# 04-Switch_RJ45.net
KiCad netlist of a schematic drawn in Altium Designer
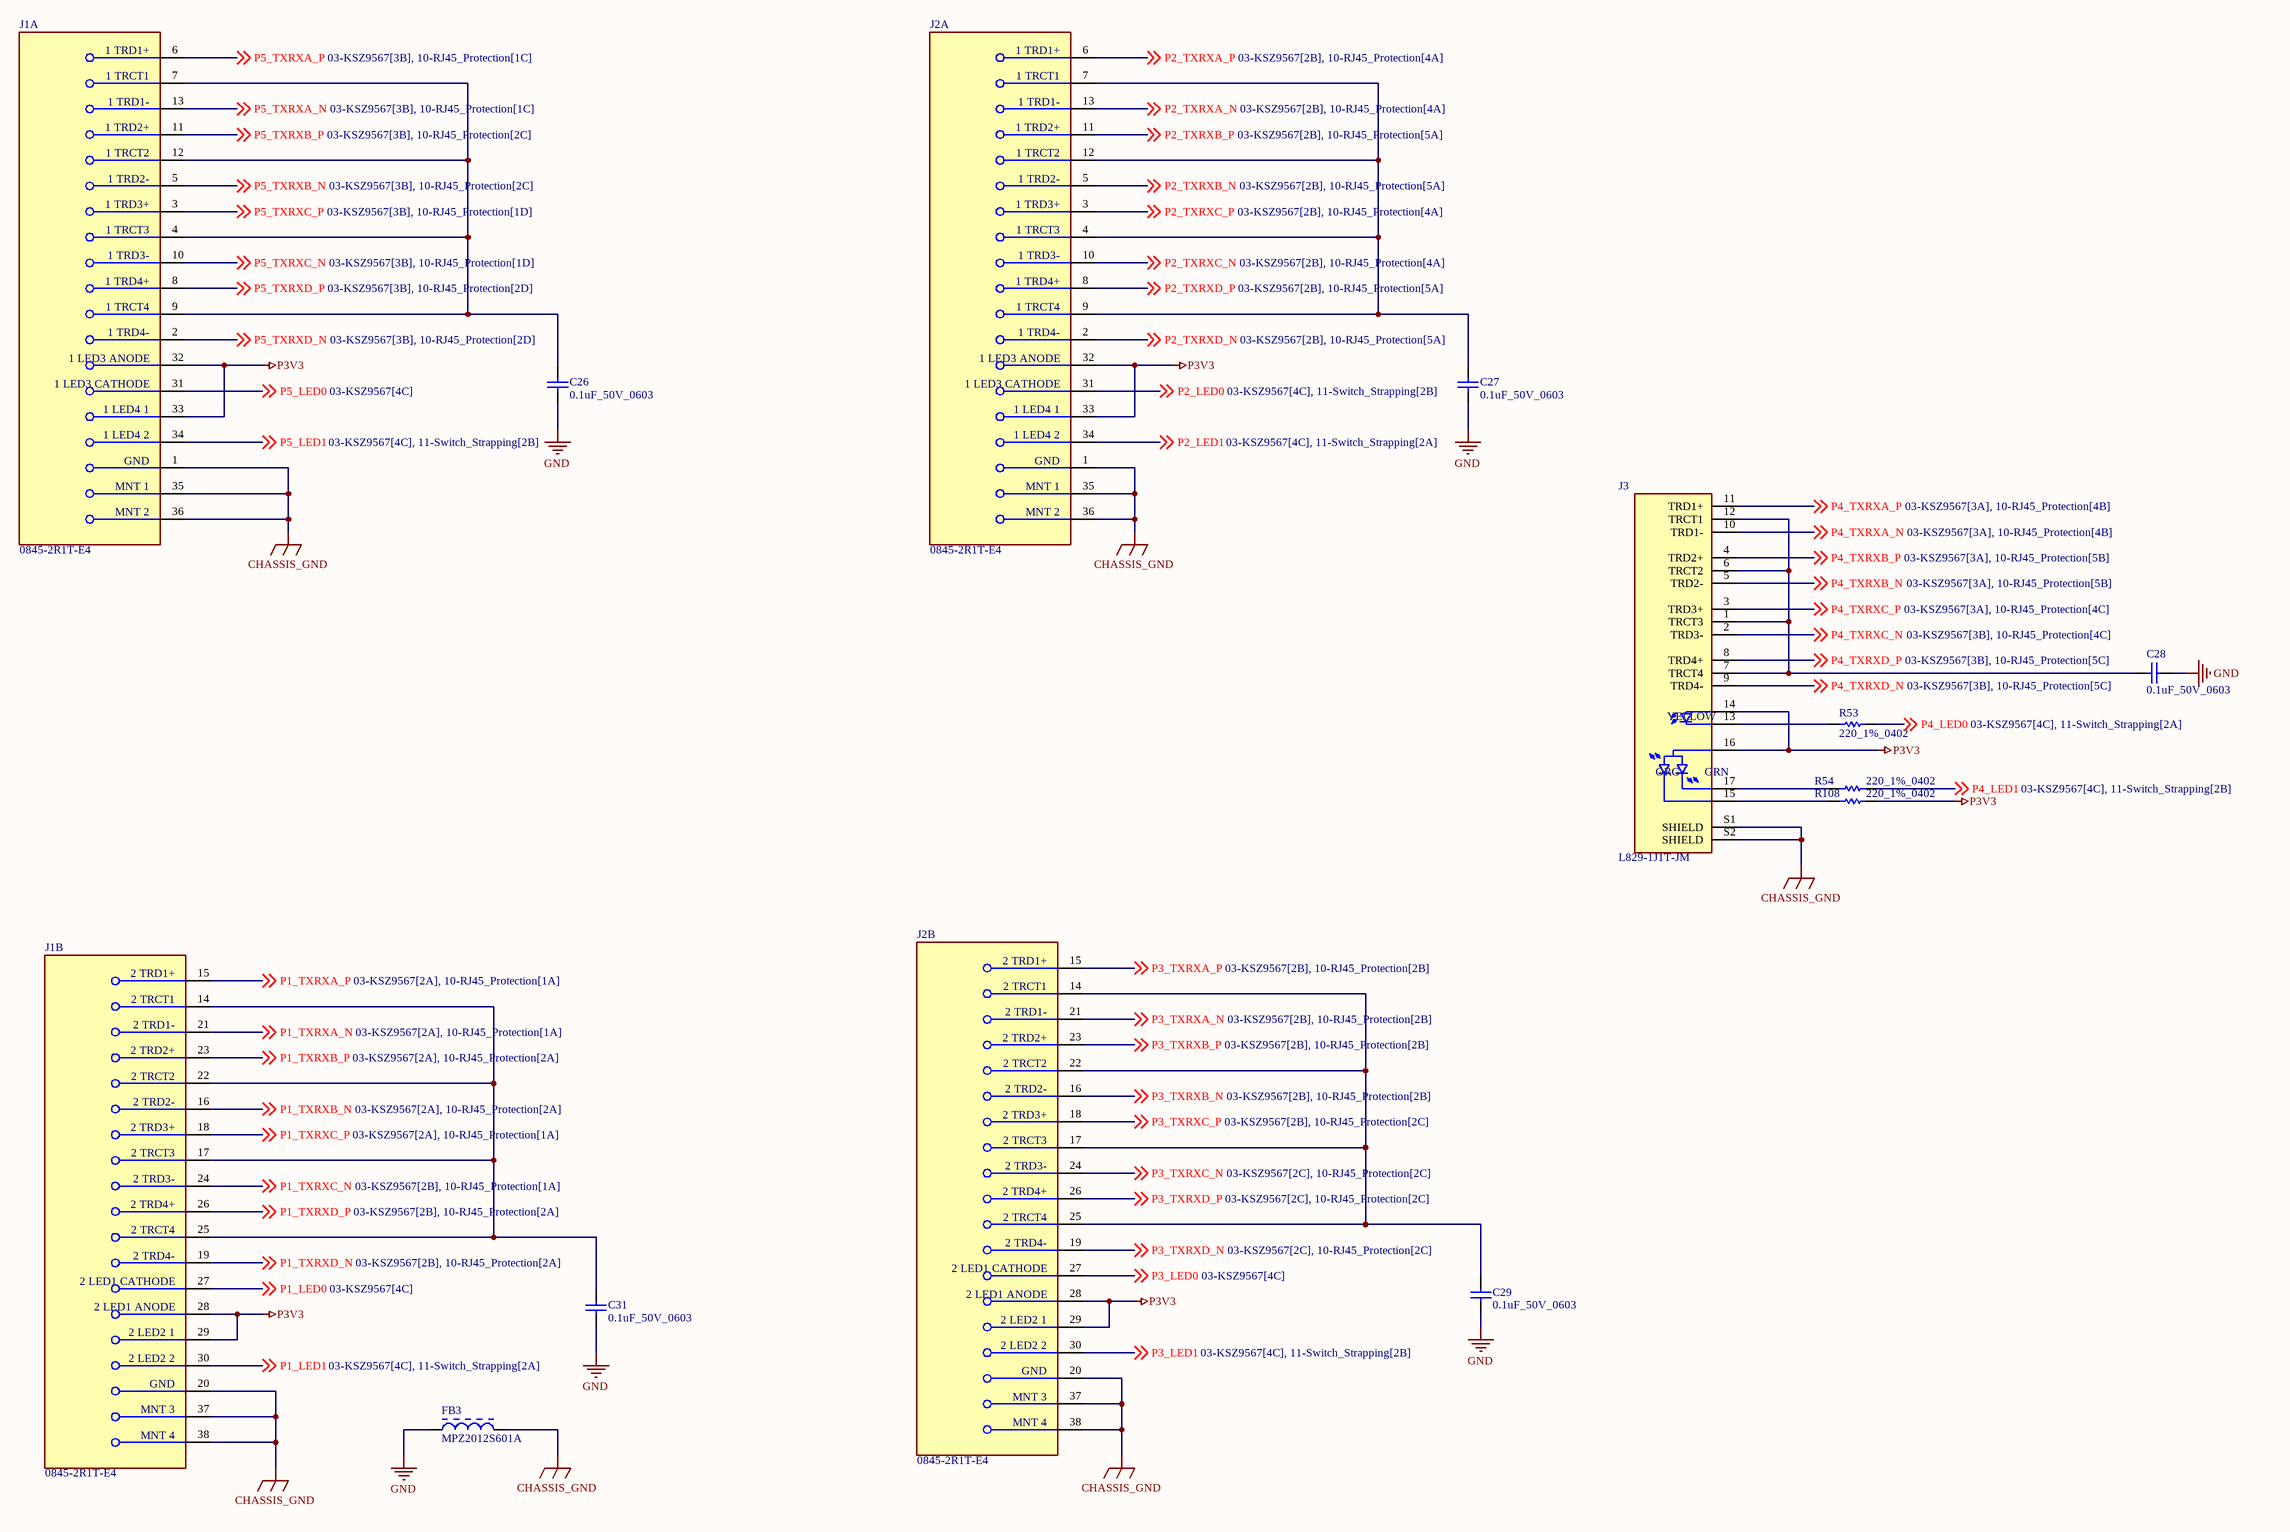
[diagram p0: 04-Switch_RJ45.SchDoc]

(export (version "E")
  (design (tool "Eeschema 10.0.6"))
  (components
    (comp (ref "C26")
      (value "0.1uF_50V_0603")
      (footprint "CAPC1608X90X35ML10T15")
      (description "Chip Capacitor, 0.1 uF, +/- 10%, 50 V, -55 to 125 degC, 0603 (1608 Metric), RoHS, Tape and Reel")
      (fields (field (name "TOLERANCE") "10%") (field (name "VOLTAGE") "50V"))
      (libsource (lib "Altium Content Vault") (part "CAP-NP-2"))
    )
    (comp (ref "C27")
      (value "0.1uF_50V_0603")
      (footprint "CAPC1608X90X35ML10T15")
      (description "Chip Capacitor, 0.1 uF, +/- 10%, 50 V, -55 to 125 degC, 0603 (1608 Metric), RoHS, Tape and Reel")
      (fields (field (name "TOLERANCE") "10%") (field (name "VOLTAGE") "50V"))
      (libsource (lib "Altium Content Vault") (part "CAP-NP-2"))
    )
    (comp (ref "C28")
      (value "0.1uF_50V_0603")
      (footprint "CAPC1608X90X35ML10T15")
      (description "Chip Capacitor, 0.1 uF, +/- 10%, 50 V, -55 to 125 degC, 0603 (1608 Metric), RoHS, Tape and Reel")
      (fields (field (name "TOLERANCE") "10%") (field (name "VOLTAGE") "50V"))
      (libsource (lib "Altium Content Vault") (part "CAP-NP-2"))
    )
    (comp (ref "C29")
      (value "0.1uF_50V_0603")
      (footprint "CAPC1608X90X35ML10T15")
      (description "Chip Capacitor, 0.1 uF, +/- 10%, 50 V, -55 to 125 degC, 0603 (1608 Metric), RoHS, Tape and Reel")
      (fields (field (name "TOLERANCE") "10%") (field (name "VOLTAGE") "50V"))
      (libsource (lib "Altium Content Vault") (part "CAP-NP-2"))
    )
    (comp (ref "C31")
      (value "0.1uF_50V_0603")
      (footprint "CAPC1608X90X35ML10T15")
      (description "Chip Capacitor, 0.1 uF, +/- 10%, 50 V, -55 to 125 degC, 0603 (1608 Metric), RoHS, Tape and Reel")
      (fields (field (name "TOLERANCE") "10%") (field (name "VOLTAGE") "50V"))
      (libsource (lib "Altium Content Vault") (part "CAP-NP-2"))
    )
    (comp (ref "FB3")
      (value "MPZ2012S601A")
      (footprint "TDK-MPZ2012_V")
      (fields (field (name "TOLERANCE") "25%") (field (name "MANUFACTURER") "TDK"))
      (libsource (lib "Altium Content Vault") (part "BEAD-2"))
    )
    (comp (ref "J1")
      (value "0845-2R1T-E4")
      (footprint "FP-0845-2R1T-E4-MFG")
      (description "CONN MAGJACK 2PORT 1000 BASE-T")
      (fields
        (field (name "MANUFACTURER") "Bel Fuse")
        (field (name "OCTOPART") "https://octopart.com/0845-2r1t-e4-bel+fuse-10528446")
      )
      (libsource (lib "Altium Content Vault") (part "f9656fd82f206e5257674b7adff4f5e"))
    )
    (comp (ref "J2")
      (value "0845-2R1T-E4")
      (footprint "FP-0845-2R1T-E4-MFG")
      (description "CONN MAGJACK 2PORT 1000 BASE-T")
      (fields
        (field (name "MANUFACTURER") "Bel Fuse")
        (field (name "OCTOPART") "https://octopart.com/0845-2r1t-e4-bel+fuse-10528446")
      )
      (libsource (lib "Altium Content Vault") (part "f9656fd82f206e5257674b7adff4f5e"))
    )
    (comp (ref "J3")
      (value "L829-1J1T-JM")
      (footprint "BEL_L829-1J1T-JM")
      (description "MagJack 2.5GBASE-T ¦ 1X1 ¦ OG/Y LED ¦ -40 to 85C ¦ RoHS")
      (fields
        (field (name "DIGI-KEY_PART_NUMBER") "507-2068-ND")
        (field (name "MF") "Bel Magnetic Solutions")
      )
      (libsource (lib "SnapEDAsch") (part "L829-1J1T-JM"))
    )
    (comp (ref "R53")
      (value "220_1%_0402")
      (footprint "RESC1005X40X25LL10T10")
      (fields (field (name "PART NUMBER") "RK73H1ETTP2200F") (field (name "MANUFACTURER") "KOA Speer"))
      (libsource (lib "Altium Content Vault") (part "RES"))
    )
    (comp (ref "R54")
      (value "220_1%_0402")
      (footprint "RESC1005X40X25LL10T10")
      (fields (field (name "PART NUMBER") "RK73H1ETTP2200F") (field (name "MANUFACTURER") "KOA Speer"))
      (libsource (lib "Altium Content Vault") (part "RES"))
    )
    (comp (ref "R108")
      (value "220_1%_0402")
      (footprint "RESC1005X40X25LL10T10")
      (fields (field (name "PART NUMBER") "RK73H1ETTP2200F") (field (name "MANUFACTURER") "KOA Speer"))
      (libsource (lib "Altium Content Vault") (part "RES"))
    )
  )
  (nets
    (net (code "1") (name "CHASSIS_GND") (class "Default")
      (node (ref "FB3") (pin "2") (pinfunction "2_2") (pintype "passive"))
      (node (ref "J1") (pin "1") (pinfunction "GND_1") (pintype "power_in"))
      (node (ref "J1") (pin "20") (pinfunction "GND_20") (pintype "power_in"))
      (node (ref "J1") (pin "35") (pinfunction "MNT_1_35") (pintype "passive"))
      (node (ref "J1") (pin "36") (pinfunction "MNT_2_36") (pintype "passive"))
      (node (ref "J1") (pin "37") (pinfunction "MNT_3_37") (pintype "passive"))
      (node (ref "J1") (pin "38") (pinfunction "MNT_4_38") (pintype "passive"))
      (node (ref "J2") (pin "1") (pinfunction "GND_1") (pintype "power_in"))
      (node (ref "J2") (pin "20") (pinfunction "GND_20") (pintype "power_in"))
      (node (ref "J2") (pin "35") (pinfunction "MNT_1_35") (pintype "passive"))
      (node (ref "J2") (pin "36") (pinfunction "MNT_2_36") (pintype "passive"))
      (node (ref "J2") (pin "37") (pinfunction "MNT_3_37") (pintype "passive"))
      (node (ref "J2") (pin "38") (pinfunction "MNT_4_38") (pintype "passive"))
      (node (ref "J3") (pin "S1") (pinfunction "SHIELD_S1") (pintype "passive"))
      (node (ref "J3") (pin "S2") (pinfunction "SHIELD_S2") (pintype "passive"))
    )
    (net (code "2") (name "GND") (class "Default")
      (node (ref "C26") (pin "1") (pinfunction "1_1") (pintype "passive"))
      (node (ref "C27") (pin "1") (pinfunction "1_1") (pintype "passive"))
      (node (ref "C28") (pin "1") (pinfunction "1_1") (pintype "passive"))
      (node (ref "C29") (pin "1") (pinfunction "1_1") (pintype "passive"))
      (node (ref "C31") (pin "1") (pinfunction "1_1") (pintype "passive"))
      (node (ref "FB3") (pin "1") (pinfunction "1_1") (pintype "passive"))
    )
    (net (code "3") (name "Net-(J1A-1_TRCT1)") (class "Default")
      (node (ref "C26") (pin "2") (pinfunction "2_2") (pintype "passive"))
      (node (ref "J1") (pin "12") (pinfunction "1_TRCT2_12") (pintype "passive"))
      (node (ref "J1") (pin "4") (pinfunction "1_TRCT3_4") (pintype "passive"))
      (node (ref "J1") (pin "7") (pinfunction "1_TRCT1_7") (pintype "passive"))
      (node (ref "J1") (pin "9") (pinfunction "1_TRCT4_9") (pintype "passive"))
    )
    (net (code "4") (name "Net-(J1B-2_TRCT1)") (class "Default")
      (node (ref "C31") (pin "2") (pinfunction "2_2") (pintype "passive"))
      (node (ref "J1") (pin "14") (pinfunction "2_TRCT1_14") (pintype "passive"))
      (node (ref "J1") (pin "17") (pinfunction "2_TRCT3_17") (pintype "passive"))
      (node (ref "J1") (pin "22") (pinfunction "2_TRCT2_22") (pintype "passive"))
      (node (ref "J1") (pin "25") (pinfunction "2_TRCT4_25") (pintype "passive"))
    )
    (net (code "5") (name "Net-(J2A-1_TRCT1)") (class "Default")
      (node (ref "C27") (pin "2") (pinfunction "2_2") (pintype "passive"))
      (node (ref "J2") (pin "12") (pinfunction "1_TRCT2_12") (pintype "passive"))
      (node (ref "J2") (pin "4") (pinfunction "1_TRCT3_4") (pintype "passive"))
      (node (ref "J2") (pin "7") (pinfunction "1_TRCT1_7") (pintype "passive"))
      (node (ref "J2") (pin "9") (pinfunction "1_TRCT4_9") (pintype "passive"))
    )
    (net (code "6") (name "Net-(J2B-2_TRCT1)") (class "Default")
      (node (ref "C29") (pin "2") (pinfunction "2_2") (pintype "passive"))
      (node (ref "J2") (pin "14") (pinfunction "2_TRCT1_14") (pintype "passive"))
      (node (ref "J2") (pin "17") (pinfunction "2_TRCT3_17") (pintype "passive"))
      (node (ref "J2") (pin "22") (pinfunction "2_TRCT2_22") (pintype "passive"))
      (node (ref "J2") (pin "25") (pinfunction "2_TRCT4_25") (pintype "passive"))
    )
    (net (code "7") (name "Net-(J3-GK_1)") (class "Default")
      (node (ref "J3") (pin "17") (pinfunction "GK_1_17") (pintype "passive"))
      (node (ref "R54") (pin "1") (pinfunction "1_1") (pintype "passive"))
    )
    (net (code "8") (name "Net-(J3-OK_1)") (class "Default")
      (node (ref "J3") (pin "15") (pinfunction "OK_1_15") (pintype "passive"))
      (node (ref "R108") (pin "1") (pinfunction "1_1") (pintype "passive"))
    )
    (net (code "9") (name "Net-(J3-TRCT1)") (class "Default")
      (node (ref "C28") (pin "2") (pinfunction "2_2") (pintype "passive"))
      (node (ref "J3") (pin "1") (pinfunction "TRCT3_1") (pintype "passive"))
      (node (ref "J3") (pin "12") (pinfunction "TRCT1_12") (pintype "passive"))
      (node (ref "J3") (pin "6") (pinfunction "TRCT2_6") (pintype "passive"))
      (node (ref "J3") (pin "7") (pinfunction "TRCT4_7") (pintype "passive"))
    )
    (net (code "10") (name "Net-(J3-YK_1)") (class "Default")
      (node (ref "J3") (pin "13") (pinfunction "YK_1_13") (pintype "passive"))
      (node (ref "R53") (pin "1") (pinfunction "1_1") (pintype "passive"))
    )
    (net (code "11") (name "P1_LED0") (class "Default")
      (node (ref "J1") (pin "27") (pinfunction "2_LED1_CATHODE_27") (pintype "passive"))
    )
    (net (code "12") (name "P1_LED1") (class "Default")
      (node (ref "J1") (pin "30") (pinfunction "2_LED2_2_30") (pintype "passive"))
    )
    (net (code "13") (name "P1_TXRXA_N") (class "Default")
      (node (ref "J1") (pin "21") (pinfunction "2_TRD1-_21") (pintype "passive"))
    )
    (net (code "14") (name "P1_TXRXA_P") (class "Default")
      (node (ref "J1") (pin "15") (pinfunction "2_TRD1+_15") (pintype "passive"))
    )
    (net (code "15") (name "P1_TXRXB_N") (class "Default")
      (node (ref "J1") (pin "16") (pinfunction "2_TRD2-_16") (pintype "passive"))
    )
    (net (code "16") (name "P1_TXRXB_P") (class "Default")
      (node (ref "J1") (pin "23") (pinfunction "2_TRD2+_23") (pintype "passive"))
    )
    (net (code "17") (name "P1_TXRXC_N") (class "Default")
      (node (ref "J1") (pin "24") (pinfunction "2_TRD3-_24") (pintype "passive"))
    )
    (net (code "18") (name "P1_TXRXC_P") (class "Default")
      (node (ref "J1") (pin "18") (pinfunction "2_TRD3+_18") (pintype "passive"))
    )
    (net (code "19") (name "P1_TXRXD_N") (class "Default")
      (node (ref "J1") (pin "19") (pinfunction "2_TRD4-_19") (pintype "passive"))
    )
    (net (code "20") (name "P1_TXRXD_P") (class "Default")
      (node (ref "J1") (pin "26") (pinfunction "2_TRD4+_26") (pintype "passive"))
    )
    (net (code "21") (name "P2_LED0") (class "Default")
      (node (ref "J2") (pin "31") (pinfunction "1_LED3_CATHODE_31") (pintype "passive"))
    )
    (net (code "22") (name "P2_LED1") (class "Default")
      (node (ref "J2") (pin "34") (pinfunction "1_LED4_2_34") (pintype "passive"))
    )
    (net (code "23") (name "P2_TXRXA_N") (class "Default")
      (node (ref "J2") (pin "13") (pinfunction "1_TRD1-_13") (pintype "passive"))
    )
    (net (code "24") (name "P2_TXRXA_P") (class "Default")
      (node (ref "J2") (pin "6") (pinfunction "1_TRD1+_6") (pintype "passive"))
    )
    (net (code "25") (name "P2_TXRXB_N") (class "Default")
      (node (ref "J2") (pin "5") (pinfunction "1_TRD2-_5") (pintype "passive"))
    )
    (net (code "26") (name "P2_TXRXB_P") (class "Default")
      (node (ref "J2") (pin "11") (pinfunction "1_TRD2+_11") (pintype "passive"))
    )
    (net (code "27") (name "P2_TXRXC_N") (class "Default")
      (node (ref "J2") (pin "10") (pinfunction "1_TRD3-_10") (pintype "passive"))
    )
    (net (code "28") (name "P2_TXRXC_P") (class "Default")
      (node (ref "J2") (pin "3") (pinfunction "1_TRD3+_3") (pintype "passive"))
    )
    (net (code "29") (name "P2_TXRXD_N") (class "Default")
      (node (ref "J2") (pin "2") (pinfunction "1_TRD4-_2") (pintype "passive"))
    )
    (net (code "30") (name "P2_TXRXD_P") (class "Default")
      (node (ref "J2") (pin "8") (pinfunction "1_TRD4+_8") (pintype "passive"))
    )
    (net (code "31") (name "P3V3") (class "Default")
      (node (ref "J1") (pin "28") (pinfunction "2_LED1_ANODE_28") (pintype "passive"))
      (node (ref "J1") (pin "29") (pinfunction "2_LED2_1_29") (pintype "passive"))
      (node (ref "J1") (pin "32") (pinfunction "1_LED3_ANODE_32") (pintype "passive"))
      (node (ref "J1") (pin "33") (pinfunction "1_LED4_1_33") (pintype "passive"))
      (node (ref "J2") (pin "28") (pinfunction "2_LED1_ANODE_28") (pintype "passive"))
      (node (ref "J2") (pin "29") (pinfunction "2_LED2_1_29") (pintype "passive"))
      (node (ref "J2") (pin "32") (pinfunction "1_LED3_ANODE_32") (pintype "passive"))
      (node (ref "J2") (pin "33") (pinfunction "1_LED4_1_33") (pintype "passive"))
      (node (ref "J3") (pin "14") (pinfunction "YA_1_14") (pintype "passive"))
      (node (ref "J3") (pin "16") (pinfunction "CA_16") (pintype "passive"))
      (node (ref "R108") (pin "2") (pinfunction "2_2") (pintype "passive"))
    )
    (net (code "32") (name "P3_LED0") (class "Default")
      (node (ref "J2") (pin "27") (pinfunction "2_LED1_CATHODE_27") (pintype "passive"))
    )
    (net (code "33") (name "P3_LED1") (class "Default")
      (node (ref "J2") (pin "30") (pinfunction "2_LED2_2_30") (pintype "passive"))
    )
    (net (code "34") (name "P3_TXRXA_N") (class "Default")
      (node (ref "J2") (pin "21") (pinfunction "2_TRD1-_21") (pintype "passive"))
    )
    (net (code "35") (name "P3_TXRXA_P") (class "Default")
      (node (ref "J2") (pin "15") (pinfunction "2_TRD1+_15") (pintype "passive"))
    )
    (net (code "36") (name "P3_TXRXB_N") (class "Default")
      (node (ref "J2") (pin "16") (pinfunction "2_TRD2-_16") (pintype "passive"))
    )
    (net (code "37") (name "P3_TXRXB_P") (class "Default")
      (node (ref "J2") (pin "23") (pinfunction "2_TRD2+_23") (pintype "passive"))
    )
    (net (code "38") (name "P3_TXRXC_N") (class "Default")
      (node (ref "J2") (pin "24") (pinfunction "2_TRD3-_24") (pintype "passive"))
    )
    (net (code "39") (name "P3_TXRXC_P") (class "Default")
      (node (ref "J2") (pin "18") (pinfunction "2_TRD3+_18") (pintype "passive"))
    )
    (net (code "40") (name "P3_TXRXD_N") (class "Default")
      (node (ref "J2") (pin "19") (pinfunction "2_TRD4-_19") (pintype "passive"))
    )
    (net (code "41") (name "P3_TXRXD_P") (class "Default")
      (node (ref "J2") (pin "26") (pinfunction "2_TRD4+_26") (pintype "passive"))
    )
    (net (code "42") (name "P4_LED0") (class "Default")
      (node (ref "R53") (pin "2") (pinfunction "2_2") (pintype "passive"))
    )
    (net (code "43") (name "P4_LED1") (class "Default")
      (node (ref "R54") (pin "2") (pinfunction "2_2") (pintype "passive"))
    )
    (net (code "44") (name "P4_TXRXA_N") (class "Default")
      (node (ref "J3") (pin "10") (pinfunction "TRD1-_10") (pintype "passive"))
    )
    (net (code "45") (name "P4_TXRXA_P") (class "Default")
      (node (ref "J3") (pin "11") (pinfunction "TRD1+_11") (pintype "passive"))
    )
    (net (code "46") (name "P4_TXRXB_N") (class "Default")
      (node (ref "J3") (pin "5") (pinfunction "TRD2-_5") (pintype "passive"))
    )
    (net (code "47") (name "P4_TXRXB_P") (class "Default")
      (node (ref "J3") (pin "4") (pinfunction "TRD2+_4") (pintype "passive"))
    )
    (net (code "48") (name "P4_TXRXC_N") (class "Default")
      (node (ref "J3") (pin "2") (pinfunction "TRD3-_2") (pintype "passive"))
    )
    (net (code "49") (name "P4_TXRXC_P") (class "Default")
      (node (ref "J3") (pin "3") (pinfunction "TRD3+_3") (pintype "passive"))
    )
    (net (code "50") (name "P4_TXRXD_N") (class "Default")
      (node (ref "J3") (pin "9") (pinfunction "TRD4-_9") (pintype "passive"))
    )
    (net (code "51") (name "P4_TXRXD_P") (class "Default")
      (node (ref "J3") (pin "8") (pinfunction "TRD4+_8") (pintype "passive"))
    )
    (net (code "52") (name "P5_LED0") (class "Default")
      (node (ref "J1") (pin "31") (pinfunction "1_LED3_CATHODE_31") (pintype "passive"))
    )
    (net (code "53") (name "P5_LED1") (class "Default")
      (node (ref "J1") (pin "34") (pinfunction "1_LED4_2_34") (pintype "passive"))
    )
    (net (code "54") (name "P5_TXRXA_N") (class "Default")
      (node (ref "J1") (pin "13") (pinfunction "1_TRD1-_13") (pintype "passive"))
    )
    (net (code "55") (name "P5_TXRXA_P") (class "Default")
      (node (ref "J1") (pin "6") (pinfunction "1_TRD1+_6") (pintype "passive"))
    )
    (net (code "56") (name "P5_TXRXB_N") (class "Default")
      (node (ref "J1") (pin "5") (pinfunction "1_TRD2-_5") (pintype "passive"))
    )
    (net (code "57") (name "P5_TXRXB_P") (class "Default")
      (node (ref "J1") (pin "11") (pinfunction "1_TRD2+_11") (pintype "passive"))
    )
    (net (code "58") (name "P5_TXRXC_N") (class "Default")
      (node (ref "J1") (pin "10") (pinfunction "1_TRD3-_10") (pintype "passive"))
    )
    (net (code "59") (name "P5_TXRXC_P") (class "Default")
      (node (ref "J1") (pin "3") (pinfunction "1_TRD3+_3") (pintype "passive"))
    )
    (net (code "60") (name "P5_TXRXD_N") (class "Default")
      (node (ref "J1") (pin "2") (pinfunction "1_TRD4-_2") (pintype "passive"))
    )
    (net (code "61") (name "P5_TXRXD_P") (class "Default")
      (node (ref "J1") (pin "8") (pinfunction "1_TRD4+_8") (pintype "passive"))
    )
  )
)
